# Sheet1.net
KiCad netlist of a schematic drawn in Altium Designer
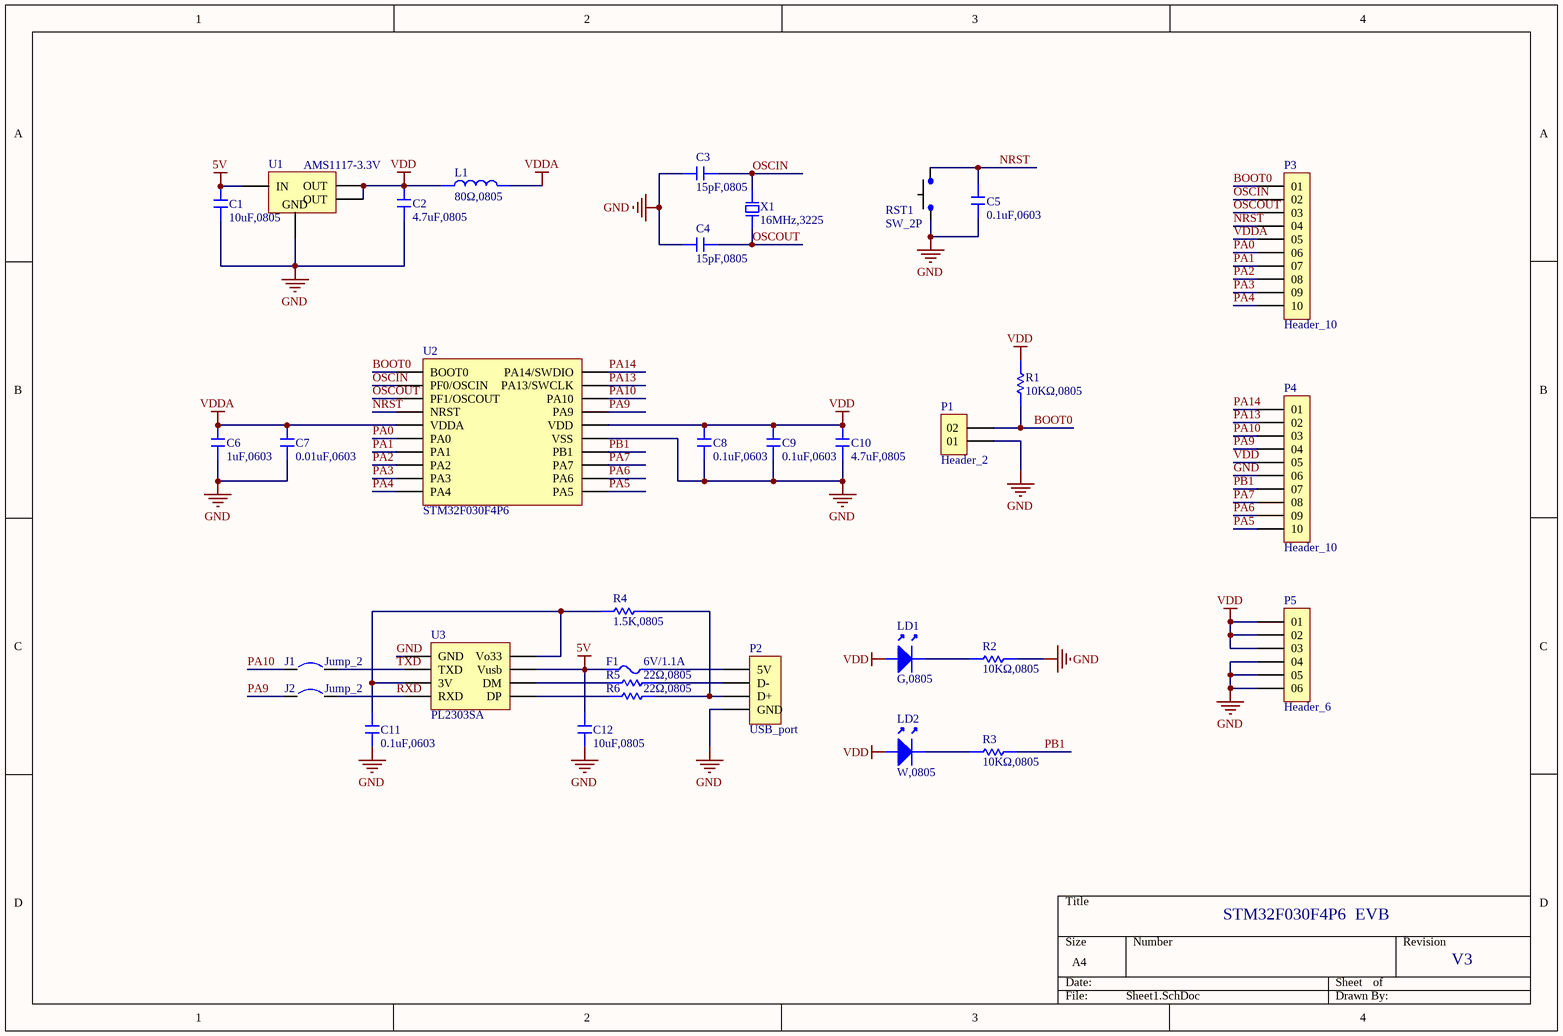
[diagram p0: Sheet1.SchDoc]

(export (version "E")
  (design (tool "Eeschema 10.0.6"))
  (components
    (comp (ref "C1") (value "10uF,0805") (footprint "C0805") (libsource (lib "myLib1") (part "Cap")))
    (comp (ref "C2") (value "4.7uF,0805") (footprint "C0805") (libsource (lib "myLib1") (part "Cap")))
    (comp (ref "C3") (value "15pF,0805") (footprint "C0805") (libsource (lib "myLib1") (part "Cap")))
    (comp (ref "C4") (value "15pF,0805") (footprint "C0805") (libsource (lib "myLib1") (part "Cap")))
    (comp (ref "C5") (value "0.1uF,0603") (footprint "C0603") (libsource (lib "myLib1") (part "Cap")))
    (comp (ref "C6") (value "1uF,0603") (footprint "C0603") (libsource (lib "myLib1") (part "Cap")))
    (comp (ref "C7") (value "0.01uF,0603") (footprint "C0603") (libsource (lib "myLib1") (part "Cap")))
    (comp (ref "C8") (value "0.1uF,0603") (footprint "C0603") (libsource (lib "myLib1") (part "Cap")))
    (comp (ref "C9") (value "0.1uF,0603") (footprint "C0603") (libsource (lib "myLib1") (part "Cap")))
    (comp (ref "C10") (value "4.7uF,0805") (footprint "C0805") (libsource (lib "myLib1") (part "Cap")))
    (comp (ref "C11") (value "0.1uF,0603") (footprint "C0603") (libsource (lib "myLib1") (part "Cap")))
    (comp (ref "C12") (value "10uF,0805") (footprint "C0805") (libsource (lib "myLib1") (part "Cap")))
    (comp (ref "F1") (value "6V/1.1A") (footprint "F0805") (libsource (lib "myLib1") (part "Fuse")))
    (comp (ref "J1") (value "Jump_2") (footprint "Jp0603") (libsource (lib "myLib1") (part "Jump_2")))
    (comp (ref "J2") (value "Jump_2") (footprint "Jp0603") (libsource (lib "myLib1") (part "Jump_2")))
    (comp (ref "L1") (value "80Ω,0805") (footprint "L0805") (libsource (lib "myLib1") (part "Ind")))
    (comp (ref "LD1") (value "G,0805") (footprint "LED0805") (libsource (lib "myLib1") (part "Diode - LED")))
    (comp (ref "LD2") (value "W,0805") (footprint "LED0805") (libsource (lib "myLib1") (part "Diode - LED")))
    (comp (ref "P1") (value "Header_2") (footprint "Header_2") (libsource (lib "myLib1") (part "Header_2")))
    (comp (ref "P2") (value "USB_port") (footprint "USB-AO") (libsource (lib "myLib1") (part "USB_port")))
    (comp (ref "P3")
      (value "Header_10")
      (footprint "Header_10")
      (libsource (lib "myLib1") (part "Header_10"))
    )
    (comp (ref "P4")
      (value "Header_10")
      (footprint "Header_10")
      (libsource (lib "myLib1") (part "Header_10"))
    )
    (comp (ref "P5") (value "Header_6") (footprint "Header_6") (libsource (lib "myLib1") (part "Header_6")))
    (comp (ref "R1") (value "10KΩ,0805") (footprint "R0805") (libsource (lib "myLib1") (part "Res")))
    (comp (ref "R2") (value "10KΩ,0805") (footprint "R0805") (libsource (lib "myLib1") (part "Res")))
    (comp (ref "R3") (value "10KΩ,0805") (footprint "R0805") (libsource (lib "myLib1") (part "Res")))
    (comp (ref "R4") (value "1.5K,0805") (footprint "R0805") (libsource (lib "myLib1") (part "Res")))
    (comp (ref "R5") (value "22Ω,0805") (footprint "R0805") (libsource (lib "myLib1") (part "Res")))
    (comp (ref "R6") (value "22Ω,0805") (footprint "R0805") (libsource (lib "myLib1") (part "Res")))
    (comp (ref "RST1") (value "SW_2P") (footprint "SW_2P_3") (libsource (lib "myLib1") (part "SW_2P")))
    (comp (ref "U1") (value "AMS1117-3.3V") (footprint "SOT-223") (libsource (lib "myLib1") (part "AMS1117")))
    (comp (ref "U2")
      (value "STM32F030F4P6")
      (footprint "TSSOP20")
      (libsource (lib "myLib1") (part "STM32F030F4P6"))
    )
    (comp (ref "U3") (value "PL2303SA") (footprint "SOP8") (libsource (lib "myLib1") (part "PL2303SA")))
    (comp (ref "X1")
      (value "16MHz,3225")
      (footprint "XTAL_SMD_3225")
      (libsource (lib "myLib1") (part "XTAL"))
    )
  )
  (nets
    (net (code "1") (name "/BOOT0") (class "Default")
      (node (ref "P1") (pin "02") (pinfunction "02_02") (pintype "passive"))
      (node (ref "P3") (pin "01") (pinfunction "01_01") (pintype "passive"))
      (node (ref "R1") (pin "01") (pintype "passive"))
      (node (ref "U2") (pin "01") (pinfunction "BOOT0_01") (pintype "passive"))
    )
    (net (code "2") (name "/NRST") (class "Default")
      (node (ref "C5") (pin "01") (pintype "passive"))
      (node (ref "P3") (pin "04") (pinfunction "04_04") (pintype "passive"))
      (node (ref "RST1") (pin "02") (pintype "passive"))
      (node (ref "U2") (pin "04") (pinfunction "NRST_04") (pintype "passive"))
    )
    (net (code "3") (name "/OSCIN") (class "Default")
      (node (ref "C3") (pin "02") (pintype "passive"))
      (node (ref "P3") (pin "02") (pinfunction "02_02") (pintype "passive"))
      (node (ref "U2") (pin "02") (pinfunction "PF0/OSCIN_02") (pintype "passive"))
      (node (ref "X1") (pin "02") (pinfunction "02_02") (pintype "passive"))
    )
    (net (code "4") (name "/OSCOUT") (class "Default")
      (node (ref "C4") (pin "01") (pintype "passive"))
      (node (ref "P3") (pin "03") (pinfunction "03_03") (pintype "passive"))
      (node (ref "U2") (pin "03") (pinfunction "PF1/OSCOUT_03") (pintype "passive"))
      (node (ref "X1") (pin "01") (pinfunction "01_01") (pintype "passive"))
    )
    (net (code "5") (name "/PA0") (class "Default")
      (node (ref "P3") (pin "06") (pinfunction "06_06") (pintype "passive"))
      (node (ref "U2") (pin "06") (pinfunction "PA0_06") (pintype "passive"))
    )
    (net (code "6") (name "/PA1") (class "Default")
      (node (ref "P3") (pin "07") (pinfunction "07_07") (pintype "passive"))
      (node (ref "U2") (pin "07") (pinfunction "PA1_07") (pintype "passive"))
    )
    (net (code "7") (name "/PA2") (class "Default")
      (node (ref "P3") (pin "08") (pinfunction "08_08") (pintype "passive"))
      (node (ref "U2") (pin "08") (pinfunction "PA2_08") (pintype "passive"))
    )
    (net (code "8") (name "/PA3") (class "Default")
      (node (ref "P3") (pin "09") (pinfunction "09_09") (pintype "passive"))
      (node (ref "U2") (pin "09") (pinfunction "PA3_09") (pintype "passive"))
    )
    (net (code "9") (name "/PA4") (class "Default")
      (node (ref "P3") (pin "10") (pinfunction "10_10") (pintype "passive"))
      (node (ref "U2") (pin "10") (pinfunction "PA4_10") (pintype "passive"))
    )
    (net (code "10") (name "/PA5") (class "Default")
      (node (ref "P4") (pin "10") (pinfunction "10_10") (pintype "passive"))
      (node (ref "U2") (pin "11") (pinfunction "PA5_11") (pintype "passive"))
    )
    (net (code "11") (name "/PA6") (class "Default")
      (node (ref "P4") (pin "09") (pinfunction "09_09") (pintype "passive"))
      (node (ref "U2") (pin "12") (pinfunction "PA6_12") (pintype "passive"))
    )
    (net (code "12") (name "/PA7") (class "Default")
      (node (ref "P4") (pin "08") (pinfunction "08_08") (pintype "passive"))
      (node (ref "U2") (pin "13") (pinfunction "PA7_13") (pintype "passive"))
    )
    (net (code "13") (name "/PA9") (class "Default")
      (node (ref "J2") (pin "01") (pinfunction "1_01") (pintype "passive"))
      (node (ref "P4") (pin "04") (pinfunction "04_04") (pintype "passive"))
      (node (ref "U2") (pin "17") (pinfunction "PA9_17") (pintype "passive"))
    )
    (net (code "14") (name "/PA10") (class "Default")
      (node (ref "J1") (pin "01") (pinfunction "1_01") (pintype "passive"))
      (node (ref "P4") (pin "03") (pinfunction "03_03") (pintype "passive"))
      (node (ref "U2") (pin "18") (pinfunction "PA10_18") (pintype "passive"))
    )
    (net (code "15") (name "/PA13") (class "Default")
      (node (ref "P4") (pin "02") (pinfunction "02_02") (pintype "passive"))
      (node (ref "U2") (pin "19") (pinfunction "PA13/SWCLK_19") (pintype "passive"))
    )
    (net (code "16") (name "/PA14") (class "Default")
      (node (ref "P4") (pin "01") (pinfunction "01_01") (pintype "passive"))
      (node (ref "U2") (pin "20") (pinfunction "PA14/SWDIO_20") (pintype "passive"))
    )
    (net (code "17") (name "/PB1") (class "Default")
      (node (ref "P4") (pin "07") (pinfunction "07_07") (pintype "passive"))
      (node (ref "R3") (pin "01") (pintype "passive"))
      (node (ref "U2") (pin "14") (pinfunction "PB1_14") (pintype "passive"))
    )
    (net (code "18") (name "/RXD") (class "Default")
      (node (ref "J2") (pin "02") (pinfunction "2_02") (pintype "passive"))
      (node (ref "U3") (pin "04") (pinfunction "RXD_04") (pintype "passive"))
    )
    (net (code "19") (name "/TXD") (class "Default")
      (node (ref "J1") (pin "02") (pinfunction "2_02") (pintype "passive"))
      (node (ref "U3") (pin "02") (pinfunction "TXD_02") (pintype "passive"))
    )
    (net (code "20") (name "5V") (class "Default")
      (node (ref "C1") (pin "01") (pintype "passive"))
      (node (ref "C12") (pin "01") (pintype "passive"))
      (node (ref "F1") (pin "01") (pintype "passive"))
      (node (ref "U1") (pin "03") (pinfunction "IN_03") (pintype "passive"))
      (node (ref "U3") (pin "07") (pinfunction "Vusb_07") (pintype "passive"))
    )
    (net (code "21") (name "GND") (class "Default")
      (node (ref "C1") (pin "02") (pintype "passive"))
      (node (ref "C10") (pin "02") (pintype "passive"))
      (node (ref "C11") (pin "02") (pintype "passive"))
      (node (ref "C12") (pin "02") (pintype "passive"))
      (node (ref "C2") (pin "02") (pintype "passive"))
      (node (ref "C3") (pin "01") (pintype "passive"))
      (node (ref "C4") (pin "02") (pintype "passive"))
      (node (ref "C5") (pin "02") (pintype "passive"))
      (node (ref "C6") (pin "02") (pintype "passive"))
      (node (ref "C7") (pin "02") (pintype "passive"))
      (node (ref "C8") (pin "02") (pintype "passive"))
      (node (ref "C9") (pin "02") (pintype "passive"))
      (node (ref "P1") (pin "01") (pinfunction "01_01") (pintype "passive"))
      (node (ref "P2") (pin "01") (pinfunction "GND_01") (pintype "passive"))
      (node (ref "P4") (pin "06") (pinfunction "06_06") (pintype "passive"))
      (node (ref "P5") (pin "04") (pinfunction "04_04") (pintype "passive"))
      (node (ref "P5") (pin "05") (pinfunction "05_05") (pintype "passive"))
      (node (ref "P5") (pin "06") (pinfunction "06_06") (pintype "passive"))
      (node (ref "R2") (pin "01") (pintype "passive"))
      (node (ref "RST1") (pin "01") (pintype "passive"))
      (node (ref "U1") (pin "01") (pinfunction "GND_01") (pintype "passive"))
      (node (ref "U2") (pin "15") (pinfunction "VSS_15") (pintype "passive"))
      (node (ref "U3") (pin "01") (pinfunction "GND_01") (pintype "passive"))
    )
    (net (code "22") (name "Net-(LD1-Pad02)") (class "Default")
      (node (ref "LD1") (pin "02") (pintype "passive"))
      (node (ref "R2") (pin "02") (pintype "passive"))
    )
    (net (code "23") (name "Net-(LD2-Pad02)") (class "Default")
      (node (ref "LD2") (pin "02") (pintype "passive"))
      (node (ref "R3") (pin "02") (pintype "passive"))
    )
    (net (code "24") (name "Net-(P2-5V)") (class "Default")
      (node (ref "F1") (pin "02") (pintype "passive"))
      (node (ref "P2") (pin "04") (pinfunction "5V_04") (pintype "passive"))
    )
    (net (code "25") (name "Net-(P2-D+)") (class "Default")
      (node (ref "P2") (pin "02") (pinfunction "D+_02") (pintype "passive"))
      (node (ref "R4") (pin "02") (pintype "passive"))
      (node (ref "R6") (pin "02") (pintype "passive"))
    )
    (net (code "26") (name "Net-(P2-D-)") (class "Default")
      (node (ref "P2") (pin "03") (pinfunction "D-_03") (pintype "passive"))
      (node (ref "R5") (pin "02") (pintype "passive"))
    )
    (net (code "27") (name "Net-(U3-3V)") (class "Default")
      (node (ref "C11") (pin "01") (pintype "passive"))
      (node (ref "R4") (pin "01") (pintype "passive"))
      (node (ref "U3") (pin "03") (pinfunction "3V_03") (pintype "passive"))
      (node (ref "U3") (pin "08") (pinfunction "Vo33_08") (pintype "passive"))
    )
    (net (code "28") (name "Net-(U3-DM)") (class "Default")
      (node (ref "R5") (pin "01") (pintype "passive"))
      (node (ref "U3") (pin "06") (pinfunction "DM_06") (pintype "passive"))
    )
    (net (code "29") (name "Net-(U3-DP)") (class "Default")
      (node (ref "R6") (pin "01") (pintype "passive"))
      (node (ref "U3") (pin "05") (pinfunction "DP_05") (pintype "passive"))
    )
    (net (code "30") (name "VDD") (class "Default")
      (node (ref "C10") (pin "01") (pintype "passive"))
      (node (ref "C2") (pin "01") (pintype "passive"))
      (node (ref "C8") (pin "01") (pintype "passive"))
      (node (ref "C9") (pin "01") (pintype "passive"))
      (node (ref "L1") (pin "01") (pinfunction "01_01") (pintype "passive"))
      (node (ref "LD1") (pin "01") (pintype "passive"))
      (node (ref "LD2") (pin "01") (pintype "passive"))
      (node (ref "P4") (pin "05") (pinfunction "05_05") (pintype "passive"))
      (node (ref "P5") (pin "01") (pinfunction "01_01") (pintype "passive"))
      (node (ref "P5") (pin "02") (pinfunction "02_02") (pintype "passive"))
      (node (ref "P5") (pin "03") (pinfunction "03_03") (pintype "passive"))
      (node (ref "R1") (pin "02") (pintype "passive"))
      (node (ref "U1") (pin "02") (pinfunction "OUT_02") (pintype "passive"))
      (node (ref "U1") (pin "04") (pinfunction "OUT_04") (pintype "passive"))
      (node (ref "U2") (pin "16") (pinfunction "VDD_16") (pintype "passive"))
    )
    (net (code "31") (name "VDDA") (class "Default")
      (node (ref "C6") (pin "01") (pintype "passive"))
      (node (ref "C7") (pin "01") (pintype "passive"))
      (node (ref "L1") (pin "02") (pinfunction "02_02") (pintype "passive"))
      (node (ref "P3") (pin "05") (pinfunction "05_05") (pintype "passive"))
      (node (ref "U2") (pin "05") (pinfunction "VDDA_05") (pintype "passive"))
    )
  )
)
